# mSD-Breakout_v10.net
KiCad netlist of a schematic drawn in EAGLE
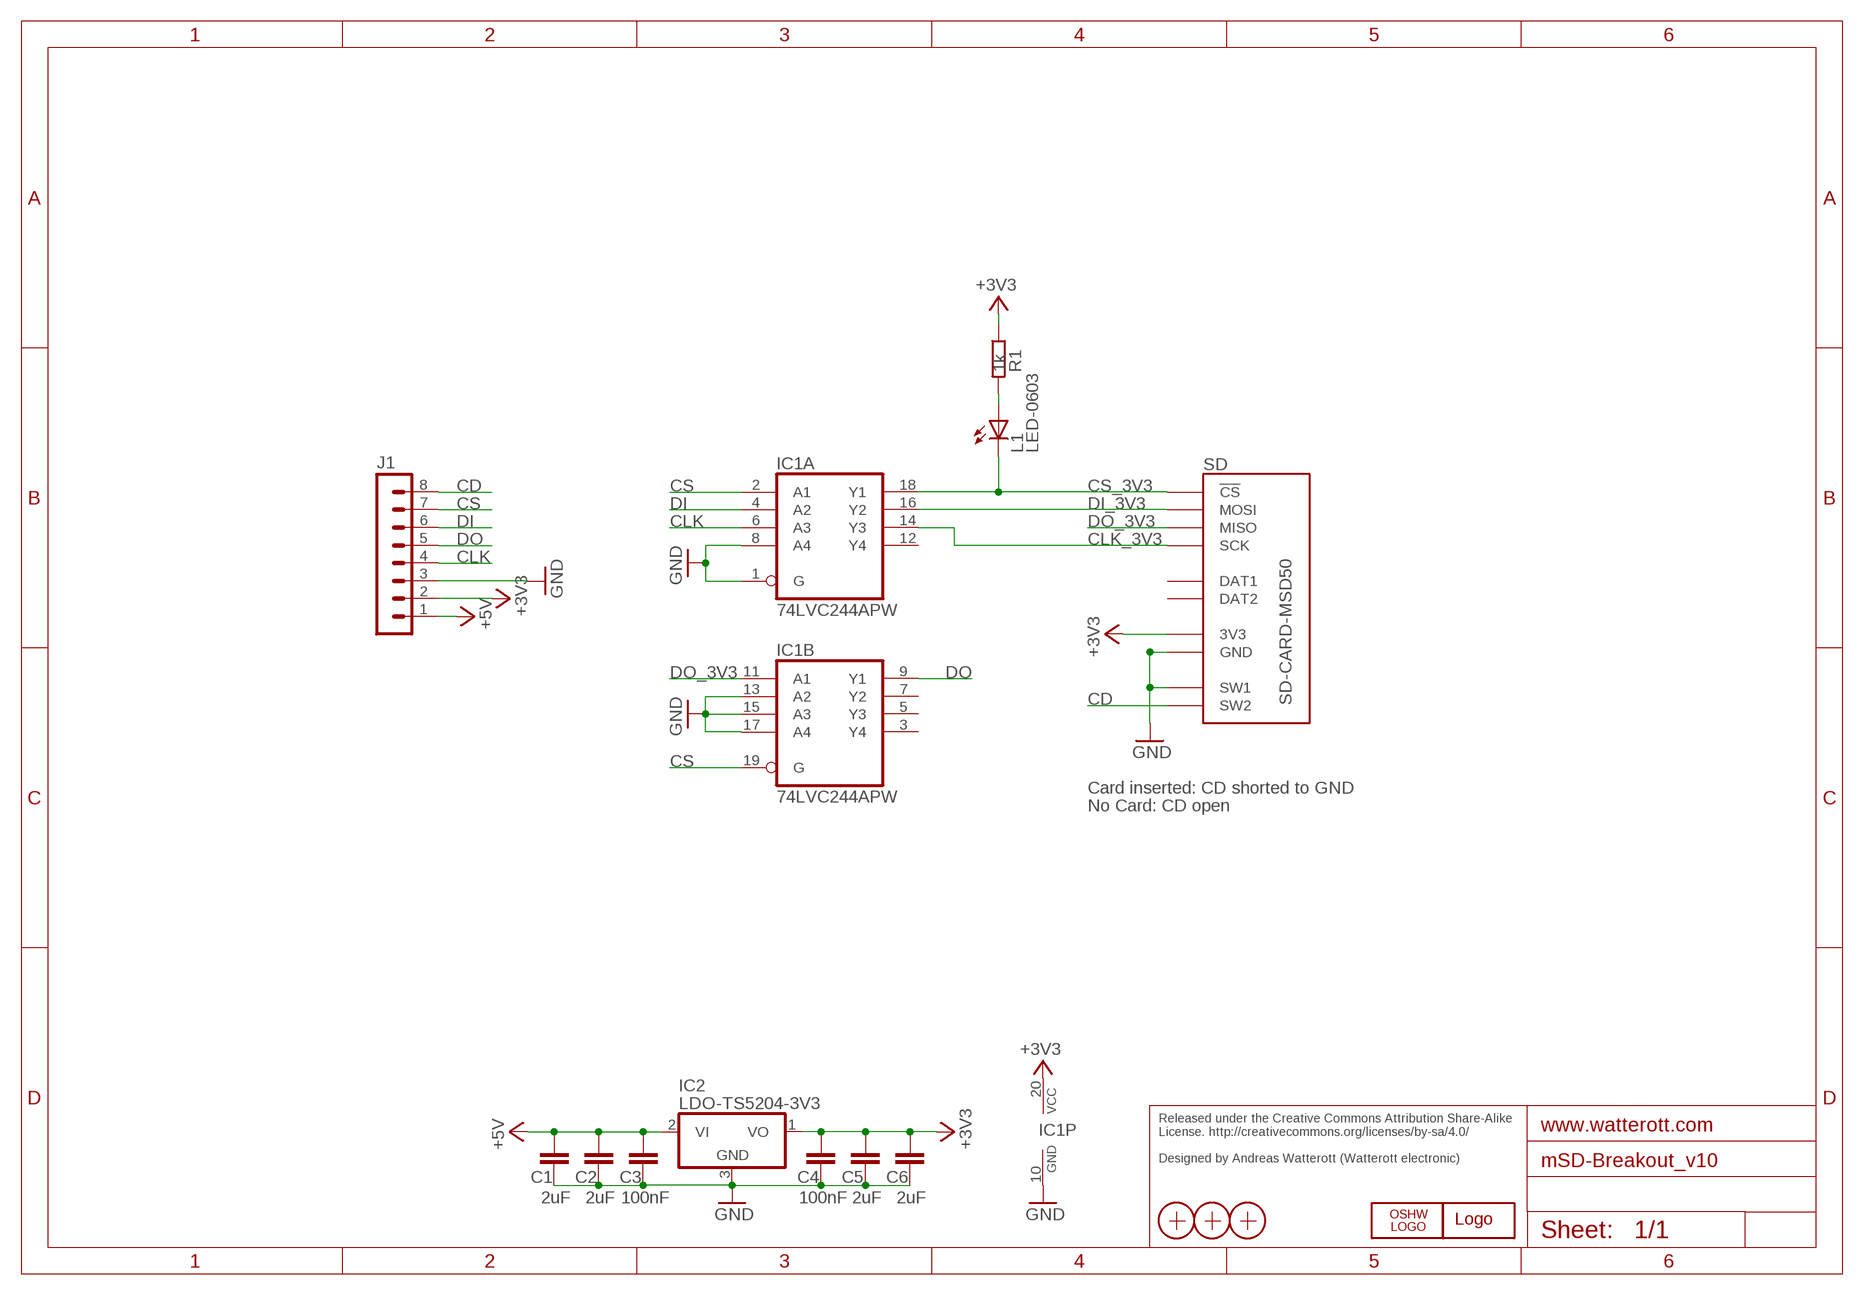
[diagram p0: schematic, sheet 1]

(export (version "E")
  (design (tool "Eeschema 10.0.6"))
  (components
    (comp (ref "C1")
      (value "2uF")
      (footprint "eagle-import:C0603")
      (libsource (lib "eagle-import") (part "C-EUC0603"))
    )
    (comp (ref "C2")
      (value "2uF")
      (footprint "eagle-import:C0603")
      (libsource (lib "eagle-import") (part "C-EUC0603"))
    )
    (comp (ref "C3")
      (value "100nF")
      (footprint "eagle-import:C0603")
      (libsource (lib "eagle-import") (part "C-EUC0603"))
    )
    (comp (ref "C4")
      (value "100nF")
      (footprint "eagle-import:C0603")
      (libsource (lib "eagle-import") (part "C-EUC0603"))
    )
    (comp (ref "C5")
      (value "2uF")
      (footprint "eagle-import:C0603")
      (libsource (lib "eagle-import") (part "C-EUC0603"))
    )
    (comp (ref "C6")
      (value "2uF")
      (footprint "eagle-import:C0603")
      (libsource (lib "eagle-import") (part "C-EUC0603"))
    )
    (comp (ref "IC1")
      (value "74LVC244APW")
      (footprint "eagle-import:TSSOP20")
      (libsource (lib "eagle-import") (part "74244PWLVC"))
    )
    (comp (ref "IC2")
      (value "LDO-TS5204-3V3")
      (footprint "eagle-import:SOT23")
      (libsource (lib "eagle-import") (part "LDO-TS5204"))
    )
    (comp (ref "J1")
      (value "MA08-1")
      (footprint "eagle-import:MA08-1")
      (libsource (lib "eagle-import") (part "MA08-1"))
    )
    (comp (ref "L1")
      (value "LED-0603")
      (footprint "eagle-import:LED_0603")
      (libsource (lib "eagle-import") (part "LED-0603"))
    )
    (comp (ref "LOGO1")
      (value "OSHW_LOGOX0100")
      (footprint "eagle-import:OSHW_6X100")
      (libsource (lib "eagle-import") (part "OSHW_LOGOX0100"))
    )
    (comp (ref "LOGO2")
      (value "LOGO-SPARK_PLACE")
      (footprint "eagle-import:SPARK_TPLACE")
      (libsource (lib "eagle-import") (part "LOGO-SPARK_PLACE"))
    )
    (comp (ref "R1")
      (value "1k")
      (footprint "eagle-import:R0603")
      (libsource (lib "eagle-import") (part "R-EU_R0603"))
    )
    (comp (ref "SD")
      (value "SD-CARD-MSD50")
      (footprint "eagle-import:SD_5031821853")
      (libsource (lib "eagle-import") (part "SD-CARD-MSD50"))
    )
    (comp (ref "X1")
      (value "PASSER")
      (footprint "eagle-import:PASSER")
      (libsource (lib "eagle-import") (part "PASSER"))
    )
    (comp (ref "X2")
      (value "PASSER")
      (footprint "eagle-import:PASSER")
      (libsource (lib "eagle-import") (part "PASSER"))
    )
    (comp (ref "X3")
      (value "PASSER")
      (footprint "eagle-import:PASSER")
      (libsource (lib "eagle-import") (part "PASSER"))
    )
  )
  (nets
    (net (code "1") (name "+3V3") (class "Default")
      (node (ref "C4") (pin "1") (pinfunction "1_1") (pintype "passive"))
      (node (ref "C5") (pin "1") (pinfunction "1_1") (pintype "passive"))
      (node (ref "C6") (pin "1") (pinfunction "1_1") (pintype "passive"))
      (node (ref "IC1") (pin "20") (pinfunction "VCC_20") (pintype "power_in"))
      (node (ref "IC2") (pin "1") (pinfunction "VO_1") (pintype "passive"))
      (node (ref "J1") (pin "2") (pinfunction "2_2") (pintype "passive"))
      (node (ref "R1") (pin "1") (pinfunction "1_1") (pintype "passive"))
      (node (ref "SD") (pin "VCC") (pinfunction "3V3_VCC") (pintype "bidirectional"))
    )
    (net (code "2") (name "+5V") (class "Default")
      (node (ref "C1") (pin "1") (pinfunction "1_1") (pintype "passive"))
      (node (ref "C2") (pin "1") (pinfunction "1_1") (pintype "passive"))
      (node (ref "C3") (pin "1") (pinfunction "1_1") (pintype "passive"))
      (node (ref "IC2") (pin "2") (pinfunction "VI_2") (pintype "input"))
      (node (ref "J1") (pin "1") (pinfunction "1_1") (pintype "passive"))
    )
    (net (code "3") (name "/CD") (class "Default")
      (node (ref "J1") (pin "8") (pinfunction "8_8") (pintype "passive"))
      (node (ref "SD") (pin "SW2") (pinfunction "SW2_SW2") (pintype "bidirectional"))
    )
    (net (code "4") (name "/CLK") (class "Default")
      (node (ref "IC1") (pin "6") (pinfunction "A3_6") (pintype "input"))
      (node (ref "J1") (pin "4") (pinfunction "4_4") (pintype "passive"))
    )
    (net (code "5") (name "/CLK_3V3") (class "Default")
      (node (ref "IC1") (pin "14") (pinfunction "Y3_14") (pintype "tri_state"))
      (node (ref "SD") (pin "SCK") (pinfunction "SCK_SCK") (pintype "bidirectional"))
    )
    (net (code "6") (name "/CS") (class "Default")
      (node (ref "IC1") (pin "19") (pinfunction "G_19") (pintype "input"))
      (node (ref "IC1") (pin "2") (pinfunction "A1_2") (pintype "input"))
      (node (ref "J1") (pin "7") (pinfunction "7_7") (pintype "passive"))
    )
    (net (code "7") (name "/CS_3V3") (class "Default")
      (node (ref "IC1") (pin "18") (pinfunction "Y1_18") (pintype "tri_state"))
      (node (ref "L1") (pin "C") (pinfunction "C_C") (pintype "passive"))
      (node (ref "SD") (pin "CS") (pinfunction "~{CS}_CS") (pintype "bidirectional"))
    )
    (net (code "8") (name "/DI") (class "Default")
      (node (ref "IC1") (pin "4") (pinfunction "A2_4") (pintype "input"))
      (node (ref "J1") (pin "6") (pinfunction "6_6") (pintype "passive"))
    )
    (net (code "9") (name "/DI_3V3") (class "Default")
      (node (ref "IC1") (pin "16") (pinfunction "Y2_16") (pintype "tri_state"))
      (node (ref "SD") (pin "MOSI") (pinfunction "MOSI_MOSI") (pintype "bidirectional"))
    )
    (net (code "10") (name "/DO") (class "Default")
      (node (ref "IC1") (pin "9") (pinfunction "Y1_9") (pintype "tri_state"))
      (node (ref "J1") (pin "5") (pinfunction "5_5") (pintype "passive"))
    )
    (net (code "11") (name "/DO_3V3") (class "Default")
      (node (ref "IC1") (pin "11") (pinfunction "A1_11") (pintype "input"))
      (node (ref "SD") (pin "MISO") (pinfunction "MISO_MISO") (pintype "bidirectional"))
    )
    (net (code "12") (name "GND") (class "Default")
      (node (ref "C1") (pin "2") (pinfunction "2_2") (pintype "passive"))
      (node (ref "C2") (pin "2") (pinfunction "2_2") (pintype "passive"))
      (node (ref "C3") (pin "2") (pinfunction "2_2") (pintype "passive"))
      (node (ref "C4") (pin "2") (pinfunction "2_2") (pintype "passive"))
      (node (ref "C5") (pin "2") (pinfunction "2_2") (pintype "passive"))
      (node (ref "C6") (pin "2") (pinfunction "2_2") (pintype "passive"))
      (node (ref "IC1") (pin "1") (pinfunction "G_1") (pintype "input"))
      (node (ref "IC1") (pin "10") (pinfunction "GND_10") (pintype "power_in"))
      (node (ref "IC1") (pin "13") (pinfunction "A2_13") (pintype "input"))
      (node (ref "IC1") (pin "15") (pinfunction "A3_15") (pintype "input"))
      (node (ref "IC1") (pin "17") (pinfunction "A4_17") (pintype "input"))
      (node (ref "IC1") (pin "8") (pinfunction "A4_8") (pintype "input"))
      (node (ref "IC2") (pin "3") (pinfunction "GND_3") (pintype "passive"))
      (node (ref "J1") (pin "3") (pinfunction "3_3") (pintype "passive"))
      (node (ref "SD") (pin "GND") (pinfunction "GND_GND") (pintype "bidirectional"))
      (node (ref "SD") (pin "SW1") (pinfunction "SW1_SW1") (pintype "bidirectional"))
    )
    (net (code "13") (name "Net-(L1-PadA)") (class "Default")
      (node (ref "L1") (pin "A") (pinfunction "A_A") (pintype "passive"))
      (node (ref "R1") (pin "2") (pinfunction "2_2") (pintype "passive"))
    )
    (net (code "14") (name "unconnected-(IC1A-Y4-Pad12)") (class "Default")
      (node (ref "IC1") (pin "12") (pinfunction "Y4_12") (pintype "tri_state"))
    )
    (net (code "15") (name "unconnected-(IC1B-Y2-Pad7)") (class "Default")
      (node (ref "IC1") (pin "7") (pinfunction "Y2_7") (pintype "tri_state"))
    )
    (net (code "16") (name "unconnected-(IC1B-Y3-Pad5)") (class "Default")
      (node (ref "IC1") (pin "5") (pinfunction "Y3_5") (pintype "tri_state"))
    )
    (net (code "17") (name "unconnected-(IC1B-Y4-Pad3)") (class "Default")
      (node (ref "IC1") (pin "3") (pinfunction "Y4_3") (pintype "tri_state"))
    )
    (net (code "18") (name "unconnected-(SD-PadDAT1)") (class "Default")
      (node (ref "SD") (pin "DAT1") (pinfunction "DAT1_DAT1") (pintype "bidirectional"))
    )
    (net (code "19") (name "unconnected-(SD-PadDAT2)") (class "Default")
      (node (ref "SD") (pin "DAT2") (pinfunction "DAT2_DAT2") (pintype "bidirectional"))
    )
  )
)
